# Std_5V.net
KiCad netlist of a schematic drawn in Altium Designer
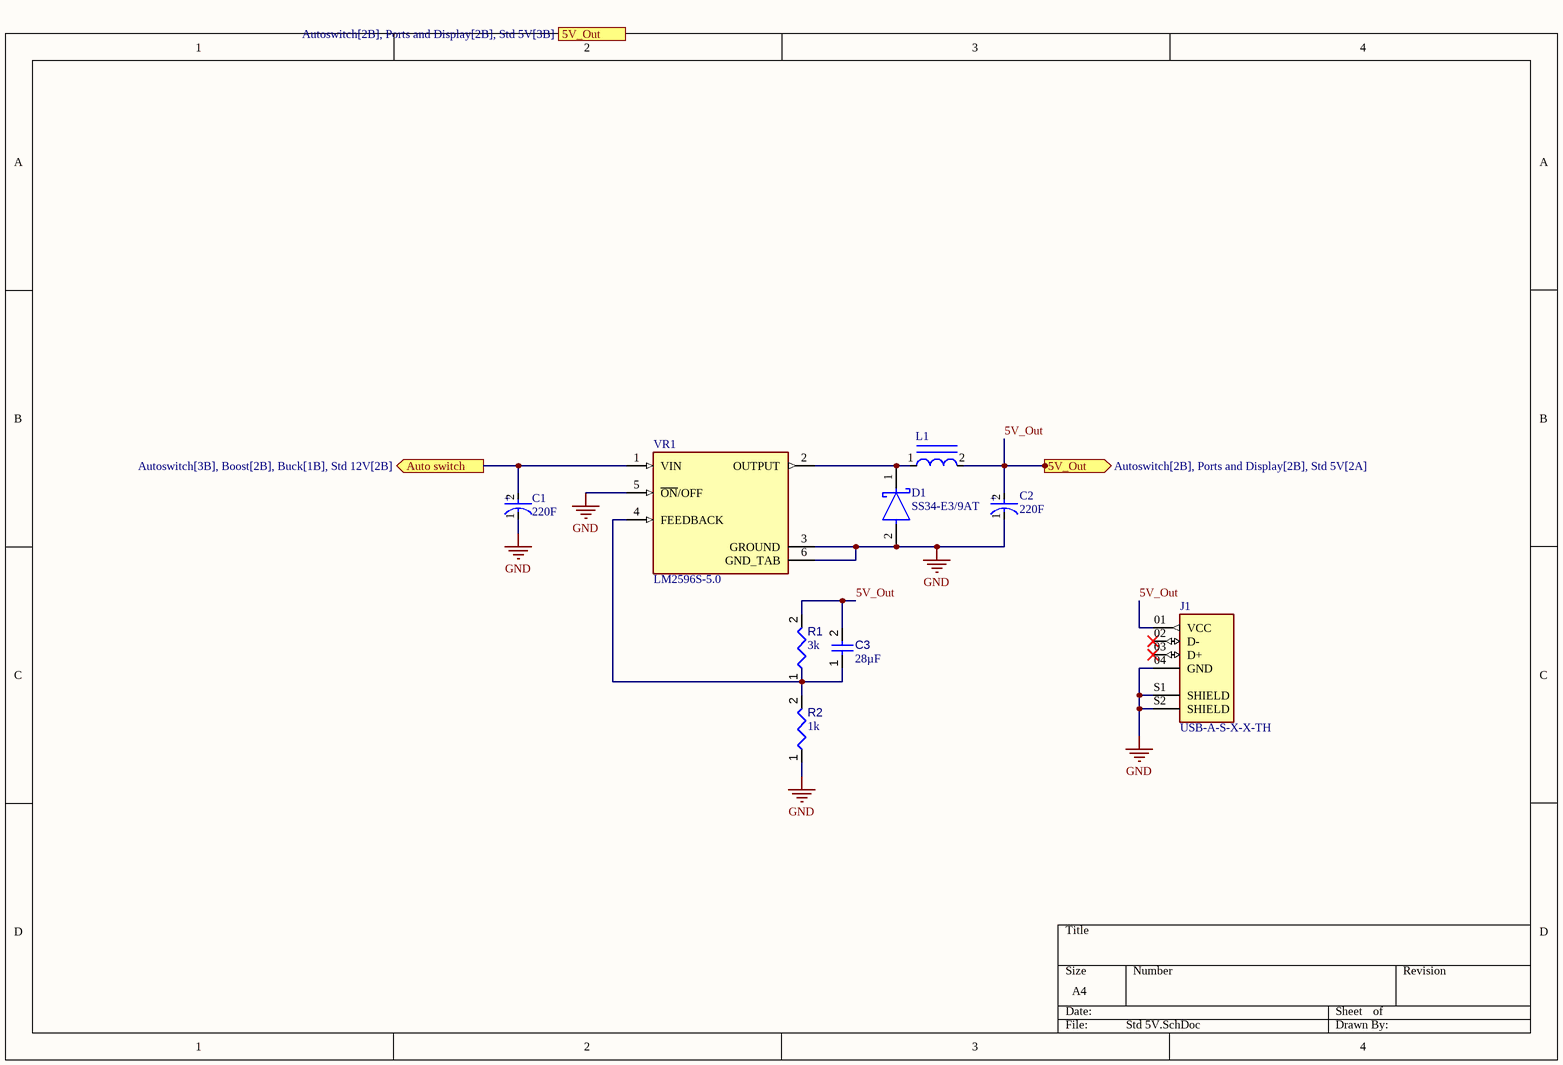
[diagram p0: Std 5V.SchDoc]

(export (version "E")
  (design (tool "Eeschema 10.0.6"))
  (components
    (comp (ref "C1")
      (value "220F")
      (footprint "FP-FTF-MFG")
      (fields (field (name "Comment") "Capacitors"))
      (libsource (lib "Vedant Ashtankar") (part "203bc49f2ac43e59fd269a8c329ed05"))
    )
    (comp (ref "C2")
      (value "220F")
      (footprint "FP-FTF-MFG")
      (fields (field (name "Comment") "Capacitors"))
      (libsource (lib "Vedant Ashtankar") (part "203bc49f2ac43e59fd269a8c329ed05"))
    )
    (comp (ref "C3")
      (value "28µF")
      (footprint "CAPC0805(2012)145_L")
      (description "Chip Capacitor, 47µF +/-40%, 6.3V, 0805, Thickness 1.45 mm")
      (fields (field (name "TOLERANCE") "10%") (field (name "Comment") "Capacitor 47µF +/-40% 6.3V 0805"))
      (libsource (lib "Vedant Ashtankar") (part "CAP-NP-2"))
    )
    (comp (ref "D1")
      (value "SS34-E3/9AT")
      (footprint "FP-SMC-MFG")
      (description "Rectifier Diode, Schottky, 1 Phase, 1 Element, 3A, 40V V(RRM), Silicon, DO-214AB")
      (libsource (lib "Vedant Ashtankar") (part "c1678fac7984e62e0809fbf79c06691"))
    )
    (comp (ref "J1")
      (value "USB-A-S-X-X-TH")
      (footprint "SAMTEC_USB-A-S-X-X-TH")
      (description "USB Connectors USB 2.0 Interface, Type A")
      (fields (field (name "MF") "Samtec") (field (name "MP") "USB-A-S-F-B-TH-TR"))
      (libsource (lib "Vedant Ashtankar") (part "USB-A-S-X-X-TH"))
    )
    (comp (ref "L1")
      (value "DR127-330-R")
      (footprint "FP-DR127-MFG")
      (description "General Purpose Inductor, 33uH, 20%, 1 Element, Ferrite-Core, SMD, 4949")
      (fields (field (name "TOLERANCE") "20%"))
      (libsource (lib "Vedant Ashtankar") (part "595efa879b4242f50b2b19a2702faec"))
    )
    (comp (ref "R1")
      (value "3k")
      (footprint "RESC0805(2012)_L")
      (description "1K 0.125W 5% 0805 (2012 Metric)  SMD")
      (fields (field (name "TOLERANCE") "5%") (field (name "POWER") "125mW"))
      (libsource (lib "Vedant Ashtankar") (part "1KR5J"))
    )
    (comp (ref "R2")
      (value "1k")
      (footprint "RESC0805(2012)_L")
      (description "1K 0.125W 5% 0805 (2012 Metric)  SMD")
      (fields (field (name "TOLERANCE") "5%") (field (name "POWER") "125mW"))
      (libsource (lib "Vedant Ashtankar") (part "1KR5J"))
    )
    (comp (ref "VR1")
      (value "LM2596S-5.0")
      (footprint "TO170P1524X483-6N")
      (description "SIMPLE SWITCHER&reg; 4.5V to 40V, 3A Low Component Count Step-Down Regulator")
      (fields (field (name "MF") "Texas Instruments") (field (name "MP") "LM2596S-5.0/NOPB"))
      (libsource (lib "Vedant Ashtankar") (part "LM2596S-5.0"))
    )
  )
  (nets
    (net (code "1") (name "/5V_Out") (class "Default")
      (node (ref "C2") (pin "2") (pinfunction "A_2") (pintype "passive"))
      (node (ref "C3") (pin "2") (pinfunction "2_2") (pintype "passive"))
      (node (ref "J1") (pin "01") (pinfunction "VCC_01") (pintype "output"))
      (node (ref "L1") (pin "2") (pinfunction "2_2") (pintype "passive"))
      (node (ref "R1") (pin "2") (pinfunction "2_2") (pintype "passive"))
    )
    (net (code "2") (name "/Auto switch") (class "Default")
      (node (ref "C1") (pin "2") (pinfunction "A_2") (pintype "passive"))
      (node (ref "VR1") (pin "1") (pinfunction "VIN_1") (pintype "input"))
    )
    (net (code "3") (name "GND") (class "Default")
      (node (ref "C1") (pin "1") (pinfunction "C_1") (pintype "passive"))
      (node (ref "C2") (pin "1") (pinfunction "C_1") (pintype "passive"))
      (node (ref "D1") (pin "2") (pinfunction "A_2") (pintype "passive"))
      (node (ref "J1") (pin "04") (pinfunction "GND_04") (pintype "power_in"))
      (node (ref "J1") (pin "S1") (pinfunction "SHIELD_S1") (pintype "passive"))
      (node (ref "J1") (pin "S2") (pinfunction "SHIELD_S2") (pintype "passive"))
      (node (ref "R2") (pin "1") (pinfunction "1_1") (pintype "passive"))
      (node (ref "VR1") (pin "3") (pinfunction "GROUND_3") (pintype "power_in"))
      (node (ref "VR1") (pin "5") (pinfunction "~{ON}/OFF_5") (pintype "input"))
      (node (ref "VR1") (pin "6") (pinfunction "GND_TAB_6") (pintype "power_in"))
    )
    (net (code "4") (name "Net-(D1-C)") (class "Default")
      (node (ref "D1") (pin "1") (pinfunction "C_1") (pintype "passive"))
      (node (ref "L1") (pin "1") (pinfunction "1_1") (pintype "passive"))
      (node (ref "VR1") (pin "2") (pinfunction "OUTPUT_2") (pintype "output"))
    )
    (net (code "5") (name "Net-(VR1-FEEDBACK)") (class "Default")
      (node (ref "C3") (pin "1") (pinfunction "1_1") (pintype "passive"))
      (node (ref "R1") (pin "1") (pinfunction "1_1") (pintype "passive"))
      (node (ref "R2") (pin "2") (pinfunction "2_2") (pintype "passive"))
      (node (ref "VR1") (pin "4") (pinfunction "FEEDBACK_4") (pintype "input"))
    )
    (net (code "6") (name "unconnected-(J1-D+-Pad03)") (class "Default")
      (node (ref "J1") (pin "03") (pinfunction "D+_03") (pintype "bidirectional+no_connect"))
    )
    (net (code "7") (name "unconnected-(J1-D--Pad02)") (class "Default")
      (node (ref "J1") (pin "02") (pinfunction "D-_02") (pintype "bidirectional+no_connect"))
    )
  )
)
